# Sheet1.net
KiCad netlist of a schematic drawn in Altium Designer
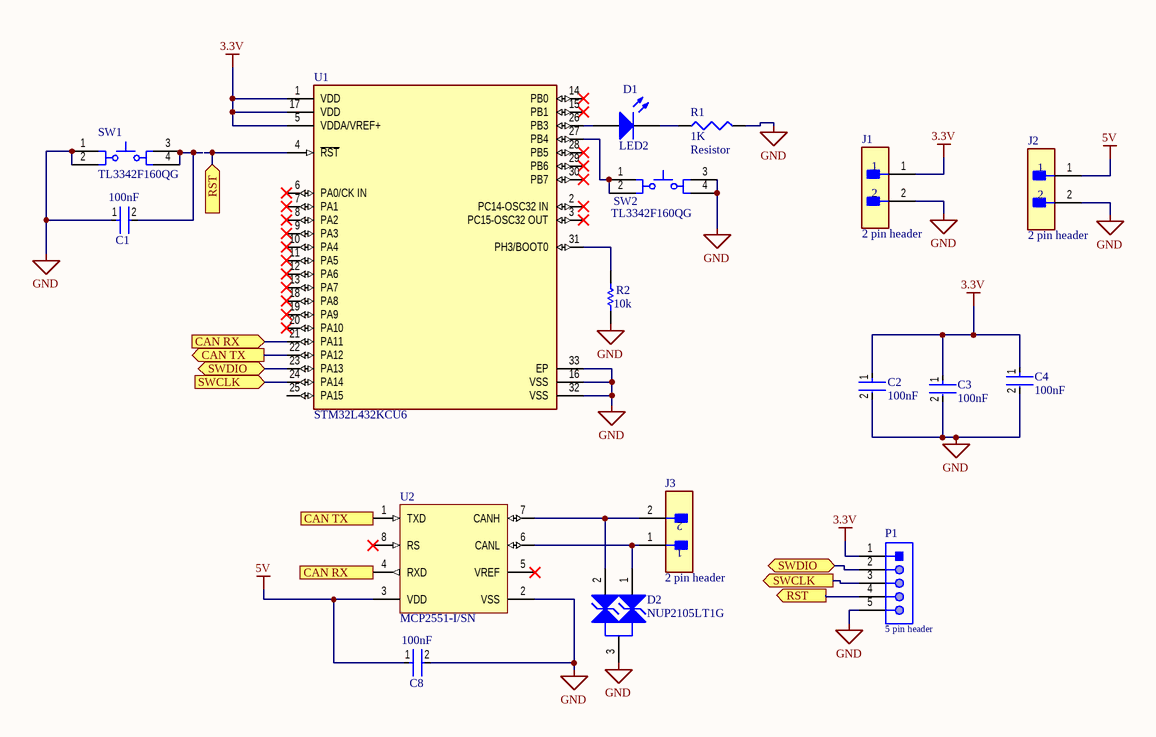
[diagram p0: Sheet1.SchDoc]

(export (version "E")
  (design (tool "Eeschema 10.0.6"))
  (components
    (comp (ref "C1")
      (value "100nF")
      (footprint "FP-CGA3E-0_3-0_1-MFG")
      (description "CGA Series 0603 100 nF 50 V ±10 % Tolerance X7R SMT Multilayer Ceramic Capacitor 100nf")
      (libsource (lib "Purdue Electric Racing") (part "b4654b650e69147ec39a6b967a45e02"))
    )
    (comp (ref "C2")
      (value "100nF")
      (footprint "FP-CGA3E-0_3-0_1-MFG")
      (description "CGA Series 0603 100 nF 50 V ±10 % Tolerance X7R SMT Multilayer Ceramic Capacitor 100nf")
      (libsource (lib "Purdue Electric Racing") (part "b4654b650e69147ec39a6b967a45e02"))
    )
    (comp (ref "C3")
      (value "100nF")
      (footprint "FP-CGA3E-0_3-0_1-MFG")
      (description "CGA Series 0603 100 nF 50 V ±10 % Tolerance X7R SMT Multilayer Ceramic Capacitor 100nf")
      (libsource (lib "Purdue Electric Racing") (part "b4654b650e69147ec39a6b967a45e02"))
    )
    (comp (ref "C4")
      (value "100nF")
      (footprint "FP-CGA3E-0_3-0_1-MFG")
      (description "CGA Series 0603 100 nF 50 V ±10 % Tolerance X7R SMT Multilayer Ceramic Capacitor 100nf")
      (libsource (lib "Purdue Electric Racing") (part "b4654b650e69147ec39a6b967a45e02"))
    )
    (comp (ref "C8")
      (value "100nF")
      (footprint "FP-CGA3E-0_3-0_1-MFG")
      (description "CGA Series 0603 100 nF 50 V ±10 % Tolerance X7R SMT Multilayer Ceramic Capacitor 100nf")
      (libsource (lib "Purdue Electric Racing") (part "b4654b650e69147ec39a6b967a45e02"))
    )
    (comp (ref "D1")
      (value "LED2")
      (footprint "3.2X1.6X1.1")
      (description "Typical RED, GREEN, YELLOW, AMBER GaAs LED")
      (fields (field (name "PUBLISHER") "Altium Limited"))
      (libsource (lib "Purdue Electric Racing") (part "Symbol"))
    )
    (comp (ref "D2")
      (value "NUP2105LT1G")
      (footprint "ONSC-SOT-23-3-318-08_V")
      (description "NUP2105L Series 350 W Dual Line CAN Bus Protector ESD Protection Diode - SOT-23")
      (libsource (lib "Purdue Electric Racing") (part "ONSC-NUP21X5X-SOT-23-3-318-08"))
    )
    (comp (ref "J1")
      (value "2 pin header")
      (footprint "FP-M20-9990246-MFG")
      (description "2.54mm (0.1\") Pitch SIL Vertical PC Tail Pin Header, 6.1mm mating pin height, tin, 2 contacts")
      (libsource (lib "Purdue Electric Racing") (part "3bc925449376181038e59eaffc5286c"))
    )
    (comp (ref "J2")
      (value "2 pin header")
      (footprint "FP-M20-9990246-MFG")
      (description "2.54mm (0.1\") Pitch SIL Vertical PC Tail Pin Header, 6.1mm mating pin height, tin, 2 contacts")
      (libsource (lib "Purdue Electric Racing") (part "3bc925449376181038e59eaffc5286c"))
    )
    (comp (ref "J3")
      (value "2 pin header")
      (footprint "FP-M20-9990246-MFG")
      (description "2.54mm (0.1\") Pitch SIL Vertical PC Tail Pin Header, 6.1mm mating pin height, tin, 2 contacts")
      (libsource (lib "") (part "3bc925449376181038e59eaffc5286c_1"))
    )
    (comp (ref "P1")
      (value "5 pin header")
      (footprint "61300511121")
      (description "THT Vertical Pin Header WR-PHD, Pitch 2.54 mm, Single Row, 5 pins")
      (libsource (lib "Purdue Electric Racing") (part "WE-CN-1P-M-R5"))
    )
    (comp (ref "R1")
      (value "1K")
      (footprint "J1-0603")
      (description "Resistor")
      (fields
        (field (name "TYPE") "Resistor")
        (field (name "Comment") "Res3")
        (field (name "PUBLISHER") "Altium Limited")
      )
      (libsource (lib "Purdue Electric Racing") (part "Res3"))
    )
    (comp (ref "R2")
      (value "10k")
      (footprint "RESC1609X50X30ML8T20")
      (description "Res Thick Film 0603 10K Ohm 1% 1/10W ±100ppm/°C Molded SMD Paper T/R")
      (libsource (lib "Purdue Electric Racing") (part "10k"))
    )
    (comp (ref "SW1")
      (value "TL3342F160QG")
      (footprint "ESWI-TL3342F160QG_V")
      (description "Switch Tactile N.O. SPST Round Button Gull Wing 0.05A 12VDC 100000Cycles 1.57N SMD T/R")
      (libsource (lib "Purdue Electric Racing") (part "SW-SPST-NO-4"))
    )
    (comp (ref "SW2")
      (value "TL3342F160QG")
      (footprint "ESWI-TL3342F160QG_V")
      (description "Switch Tactile N.O. SPST Round Button Gull Wing 0.05A 12VDC 100000Cycles 1.57N SMD T/R")
      (libsource (lib "Purdue Electric Racing") (part "SW-SPST-NO-4"))
    )
    (comp (ref "U1")
      (value "STM32L432KCU6")
      (footprint "FP-UFQFPN32-A0B8-MFG")
      (description "MCU 32-bit Ultra Low Power STM32L ARM Cortex-M4 RISC 256kB Flash 32-Pin QFN ECOPACK2 Tray")
      (libsource (lib "Purdue Electric Racing") (part "f3240dca552e0aa49c1b4baba198c12"))
    )
    (comp (ref "U2")
      (value "MCP2551-I/SN")
      (footprint "MCHP-SN8_V")
      (description "MCP2551 Series 5V 1 Mb/s Surface Mount High-Speed CAN Transceiver - SOIC-8")
      (libsource (lib "Purdue Electric Racing") (part "MCHP-MCP2551-SN8"))
    )
  )
  (nets
    (net (code "1") (name "/CAN RX") (class "Default")
      (node (ref "U1") (pin "21") (pinfunction "PA11_21") (pintype "bidirectional"))
      (node (ref "U2") (pin "4") (pinfunction "RXD_4") (pintype "output"))
    )
    (net (code "2") (name "/CAN TX") (class "Default")
      (node (ref "U1") (pin "22") (pinfunction "PA12_22") (pintype "bidirectional"))
      (node (ref "U2") (pin "1") (pinfunction "TXD_1") (pintype "input"))
    )
    (net (code "3") (name "/RST") (class "Default")
      (node (ref "P1") (pin "4") (pinfunction "4_4") (pintype "passive"))
      (node (ref "U1") (pin "4") (pinfunction "~{RST}_4") (pintype "input"))
    )
    (net (code "4") (name "/SWCLK") (class "Default")
      (node (ref "P1") (pin "3") (pinfunction "3_3") (pintype "passive"))
      (node (ref "U1") (pin "24") (pinfunction "PA14_24") (pintype "bidirectional"))
    )
    (net (code "5") (name "/SWDIO") (class "Default")
      (node (ref "P1") (pin "2") (pinfunction "2_2") (pintype "passive"))
      (node (ref "U1") (pin "23") (pinfunction "PA13_23") (pintype "bidirectional"))
    )
    (net (code "6") (name "3.3V") (class "Default")
      (node (ref "C2") (pin "1") (pinfunction "1_1") (pintype "passive"))
      (node (ref "C3") (pin "1") (pinfunction "1_1") (pintype "passive"))
      (node (ref "C4") (pin "1") (pinfunction "1_1") (pintype "passive"))
      (node (ref "J1") (pin "1") (pinfunction "1_1") (pintype "passive"))
      (node (ref "P1") (pin "1") (pinfunction "1_1") (pintype "passive"))
      (node (ref "U1") (pin "1") (pinfunction "VDD_1") (pintype "power_in"))
      (node (ref "U1") (pin "17") (pinfunction "VDD_17") (pintype "power_in"))
      (node (ref "U1") (pin "5") (pinfunction "VDDA/VREF+_5") (pintype "power_in"))
    )
    (net (code "7") (name "5V") (class "Default")
      (node (ref "C8") (pin "1") (pinfunction "1_1") (pintype "passive"))
      (node (ref "J2") (pin "1") (pinfunction "1_1") (pintype "passive"))
      (node (ref "U2") (pin "3") (pinfunction "VDD_3") (pintype "power_in"))
    )
    (net (code "8") (name "GND") (class "Default")
      (node (ref "C1") (pin "1") (pinfunction "1_1") (pintype "passive"))
      (node (ref "C2") (pin "2") (pinfunction "2_2") (pintype "passive"))
      (node (ref "C3") (pin "2") (pinfunction "2_2") (pintype "passive"))
      (node (ref "C4") (pin "2") (pinfunction "2_2") (pintype "passive"))
      (node (ref "C8") (pin "2") (pinfunction "2_2") (pintype "passive"))
      (node (ref "D2") (pin "3") (pinfunction "K_3") (pintype "passive"))
      (node (ref "J1") (pin "2") (pinfunction "2_2") (pintype "passive"))
      (node (ref "J2") (pin "2") (pinfunction "2_2") (pintype "passive"))
      (node (ref "P1") (pin "5") (pinfunction "5_5") (pintype "passive"))
      (node (ref "R1") (pin "2") (pinfunction "2_2") (pintype "passive"))
      (node (ref "R2") (pin "1") (pinfunction "1_1") (pintype "passive"))
      (node (ref "SW1") (pin "1") (pinfunction "1_1") (pintype "passive"))
      (node (ref "SW1") (pin "2") (pinfunction "2_2") (pintype "passive"))
      (node (ref "SW2") (pin "3") (pinfunction "3_3") (pintype "passive"))
      (node (ref "SW2") (pin "4") (pinfunction "4_4") (pintype "passive"))
      (node (ref "U1") (pin "16") (pinfunction "VSS_16") (pintype "power_in"))
      (node (ref "U1") (pin "32") (pinfunction "VSS_32") (pintype "power_in"))
      (node (ref "U1") (pin "33") (pinfunction "EP_33") (pintype "power_in"))
      (node (ref "U2") (pin "2") (pinfunction "VSS_2") (pintype "power_in"))
    )
    (net (code "9") (name "Net-(C1-Pad2)") (class "Default")
      (node (ref "C1") (pin "2") (pinfunction "2_2") (pintype "passive"))
      (node (ref "SW1") (pin "3") (pinfunction "3_3") (pintype "passive"))
      (node (ref "SW1") (pin "4") (pinfunction "4_4") (pintype "passive"))
    )
    (net (code "10") (name "Net-(D1-A)") (class "Default")
      (node (ref "D1") (pin "1") (pinfunction "A_1") (pintype "passive"))
      (node (ref "U1") (pin "26") (pinfunction "PB3_26") (pintype "bidirectional"))
    )
    (net (code "11") (name "Net-(D1-K)") (class "Default")
      (node (ref "D1") (pin "2") (pinfunction "K_2") (pintype "passive"))
      (node (ref "R1") (pin "1") (pinfunction "1_1") (pintype "passive"))
    )
    (net (code "12") (name "Net-(U1-PB4)") (class "Default")
      (node (ref "SW2") (pin "1") (pinfunction "1_1") (pintype "passive"))
      (node (ref "SW2") (pin "2") (pinfunction "2_2") (pintype "passive"))
      (node (ref "U1") (pin "27") (pinfunction "PB4_27") (pintype "bidirectional"))
    )
    (net (code "13") (name "Net-(U1-PH3{slash}BOOT0)") (class "Default")
      (node (ref "R2") (pin "2") (pinfunction "2_2") (pintype "passive"))
      (node (ref "U1") (pin "31") (pinfunction "PH3/BOOT0_31") (pintype "bidirectional"))
    )
    (net (code "14") (name "Net-(U2-CANH)") (class "Default")
      (node (ref "D2") (pin "2") (pinfunction "K_2") (pintype "passive"))
      (node (ref "J3") (pin "2") (pinfunction "2_2") (pintype "passive"))
      (node (ref "U2") (pin "7") (pinfunction "CANH_7") (pintype "bidirectional"))
    )
    (net (code "15") (name "Net-(U2-CANL)") (class "Default")
      (node (ref "D2") (pin "1") (pinfunction "K_1") (pintype "passive"))
      (node (ref "J3") (pin "1") (pinfunction "1_1") (pintype "passive"))
      (node (ref "U2") (pin "6") (pinfunction "CANL_6") (pintype "bidirectional"))
    )
    (net (code "16") (name "unconnected-(U1-PA0{slash}CK_IN-Pad6)") (class "Default")
      (node (ref "U1") (pin "6") (pinfunction "PA0/CK_IN_6") (pintype "bidirectional+no_connect"))
    )
    (net (code "17") (name "unconnected-(U1-PA1-Pad7)") (class "Default")
      (node (ref "U1") (pin "7") (pinfunction "PA1_7") (pintype "bidirectional+no_connect"))
    )
    (net (code "18") (name "unconnected-(U1-PA2-Pad8)") (class "Default")
      (node (ref "U1") (pin "8") (pinfunction "PA2_8") (pintype "bidirectional+no_connect"))
    )
    (net (code "19") (name "unconnected-(U1-PA3-Pad9)") (class "Default")
      (node (ref "U1") (pin "9") (pinfunction "PA3_9") (pintype "bidirectional+no_connect"))
    )
    (net (code "20") (name "unconnected-(U1-PA4-Pad10)") (class "Default")
      (node (ref "U1") (pin "10") (pinfunction "PA4_10") (pintype "bidirectional+no_connect"))
    )
    (net (code "21") (name "unconnected-(U1-PA5-Pad11)") (class "Default")
      (node (ref "U1") (pin "11") (pinfunction "PA5_11") (pintype "bidirectional+no_connect"))
    )
    (net (code "22") (name "unconnected-(U1-PA6-Pad12)") (class "Default")
      (node (ref "U1") (pin "12") (pinfunction "PA6_12") (pintype "bidirectional+no_connect"))
    )
    (net (code "23") (name "unconnected-(U1-PA7-Pad13)") (class "Default")
      (node (ref "U1") (pin "13") (pinfunction "PA7_13") (pintype "bidirectional+no_connect"))
    )
    (net (code "24") (name "unconnected-(U1-PA8-Pad18)") (class "Default")
      (node (ref "U1") (pin "18") (pinfunction "PA8_18") (pintype "bidirectional+no_connect"))
    )
    (net (code "25") (name "unconnected-(U1-PA9-Pad19)") (class "Default")
      (node (ref "U1") (pin "19") (pinfunction "PA9_19") (pintype "bidirectional+no_connect"))
    )
    (net (code "26") (name "unconnected-(U1-PA10-Pad20)") (class "Default")
      (node (ref "U1") (pin "20") (pinfunction "PA10_20") (pintype "bidirectional+no_connect"))
    )
    (net (code "27") (name "unconnected-(U1-PA15-Pad25)") (class "Default")
      (node (ref "U1") (pin "25") (pinfunction "PA15_25") (pintype "bidirectional"))
    )
    (net (code "28") (name "unconnected-(U1-PB0-Pad14)") (class "Default")
      (node (ref "U1") (pin "14") (pinfunction "PB0_14") (pintype "bidirectional+no_connect"))
    )
    (net (code "29") (name "unconnected-(U1-PB1-Pad15)") (class "Default")
      (node (ref "U1") (pin "15") (pinfunction "PB1_15") (pintype "bidirectional+no_connect"))
    )
    (net (code "30") (name "unconnected-(U1-PB5-Pad28)") (class "Default")
      (node (ref "U1") (pin "28") (pinfunction "PB5_28") (pintype "bidirectional+no_connect"))
    )
    (net (code "31") (name "unconnected-(U1-PB6-Pad29)") (class "Default")
      (node (ref "U1") (pin "29") (pinfunction "PB6_29") (pintype "bidirectional+no_connect"))
    )
    (net (code "32") (name "unconnected-(U1-PB7-Pad30)") (class "Default")
      (node (ref "U1") (pin "30") (pinfunction "PB7_30") (pintype "bidirectional+no_connect"))
    )
    (net (code "33") (name "unconnected-(U1-PC14-OSC32_IN-Pad2)") (class "Default")
      (node (ref "U1") (pin "2") (pinfunction "PC14-OSC32_IN_2") (pintype "bidirectional+no_connect"))
    )
    (net (code "34") (name "unconnected-(U1-PC15-OSC32_OUT-Pad3)") (class "Default")
      (node (ref "U1") (pin "3") (pinfunction "PC15-OSC32_OUT_3") (pintype "bidirectional+no_connect"))
    )
    (net (code "35") (name "unconnected-(U2-RS-Pad8)") (class "Default")
      (node (ref "U2") (pin "8") (pinfunction "RS_8") (pintype "input+no_connect"))
    )
    (net (code "36") (name "unconnected-(U2-VREF-Pad5)") (class "Default")
      (node (ref "U2") (pin "5") (pinfunction "VREF_5") (pintype "power_in+no_connect"))
    )
  )
)
